# CC2640.net
KiCad netlist of a schematic drawn in Altium Designer
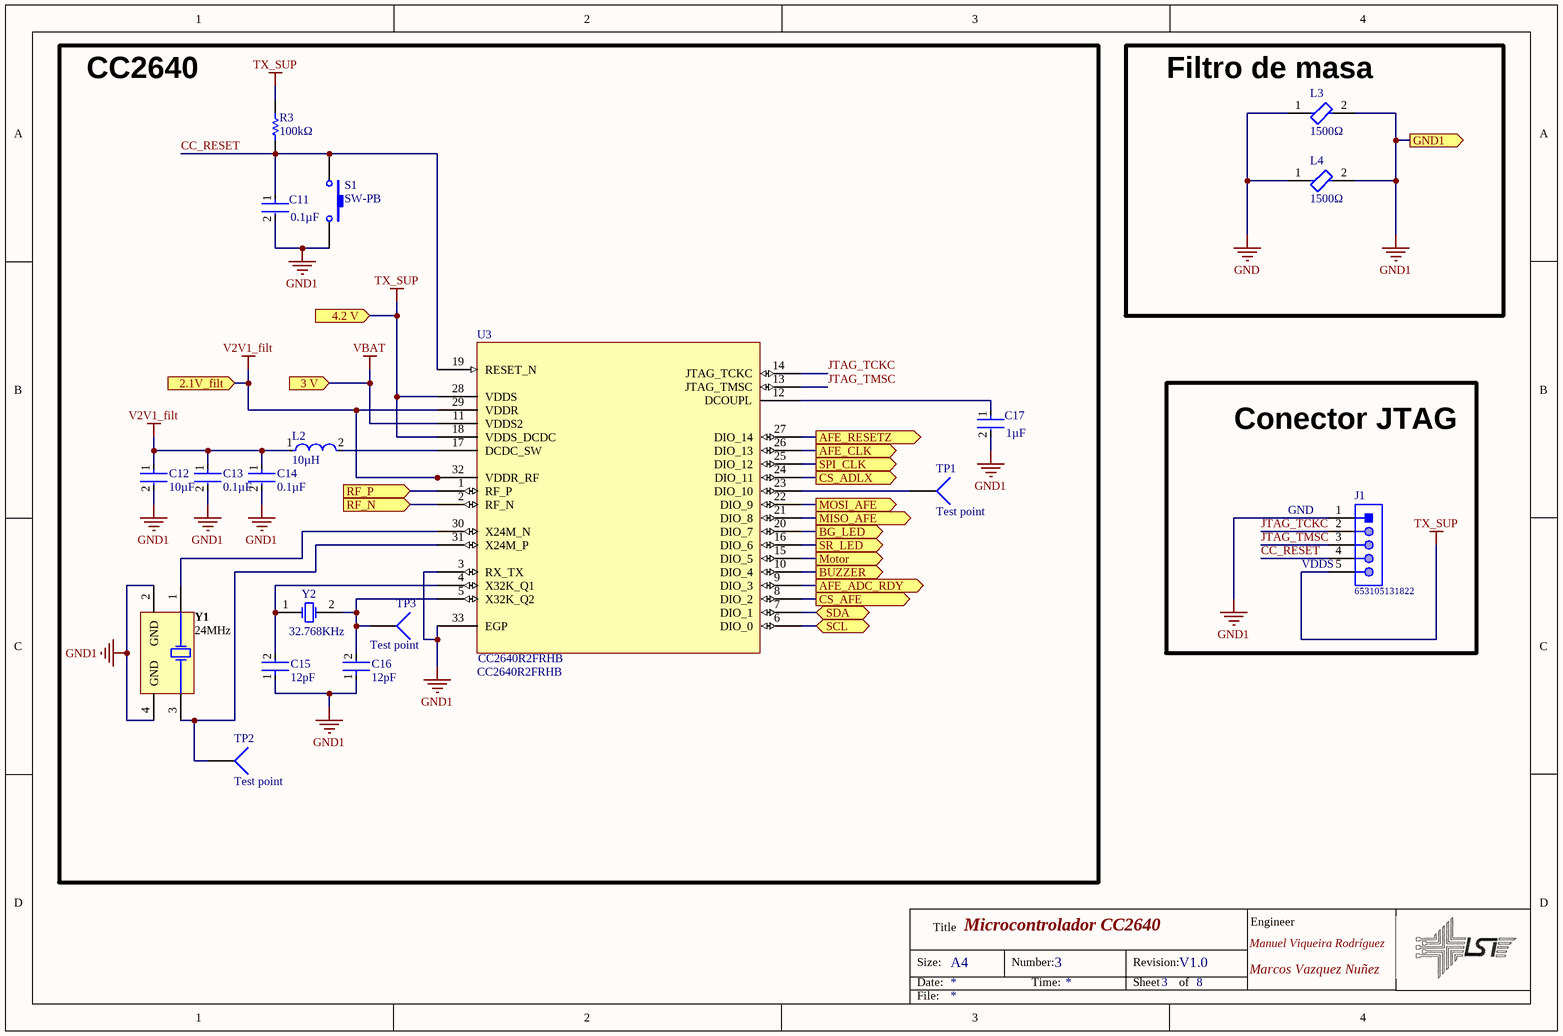
[diagram p0: CC2640.SchDoc]

(export (version "E")
  (design (tool "Eeschema 10.0.6"))
  (components
    (comp (ref "C11")
      (value "0.1µF")
      (footprint "FP-CL10-IPC_B")
      (description "Cap Ceramic 10uF 10V X5R ±10% Pad SMD 0603 +85°C T/R")
      (fields (field (name "TOLERANCE") "10%"))
      (libsource (lib "Altium Content Vault") (part "b4654b650e69147ec39a6b967a45e02"))
    )
    (comp (ref "C12")
      (value "10µF")
      (footprint "FP-CL10-IPC_B")
      (description "Cap Ceramic 10uF 10V X5R ±10% Pad SMD 0603 +85°C T/R")
      (fields (field (name "TOLERANCE") "10%"))
      (libsource (lib "Altium Content Vault") (part "b4654b650e69147ec39a6b967a45e02"))
    )
    (comp (ref "C13")
      (value "0.1µF")
      (footprint "FP-CL10-IPC_B")
      (description "Cap Ceramic 10uF 10V X5R ±10% Pad SMD 0603 +85°C T/R")
      (fields (field (name "TOLERANCE") "10%"))
      (libsource (lib "Altium Content Vault") (part "b4654b650e69147ec39a6b967a45e02"))
    )
    (comp (ref "C14")
      (value "0.1µF")
      (footprint "FP-CL10-IPC_B")
      (description "Cap Ceramic 10uF 10V X5R ±10% Pad SMD 0603 +85°C T/R")
      (fields (field (name "TOLERANCE") "10%"))
      (libsource (lib "Altium Content Vault") (part "b4654b650e69147ec39a6b967a45e02"))
    )
    (comp (ref "C15")
      (value "12pF")
      (footprint "FP-CL10-IPC_B")
      (description "Cap Ceramic 10uF 10V X5R ±10% Pad SMD 0603 +85°C T/R")
      (fields (field (name "TOLERANCE") "10%"))
      (libsource (lib "Altium Content Vault") (part "b4654b650e69147ec39a6b967a45e02"))
    )
    (comp (ref "C16")
      (value "12pF")
      (footprint "FP-CL10-IPC_B")
      (description "Cap Ceramic 10uF 10V X5R ±10% Pad SMD 0603 +85°C T/R")
      (fields (field (name "TOLERANCE") "10%"))
      (libsource (lib "Altium Content Vault") (part "b4654b650e69147ec39a6b967a45e02"))
    )
    (comp (ref "C17")
      (value "1µF")
      (footprint "FP-CL10-IPC_B")
      (description "Cap Ceramic 10uF 10V X5R ±10% Pad SMD 0603 +85°C T/R")
      (fields (field (name "TOLERANCE") "10%"))
      (libsource (lib "Altium Content Vault") (part "b4654b650e69147ec39a6b967a45e02"))
    )
    (comp (ref "J1")
      (value "653105131822")
      (footprint "653105131822")
      (description "Male Shrouded Header WR-WTB, SMT, Right Angled, pitch 1.25 mm, 1 x 5 position")
      (fields (field (name "MANUFACTURER") "Wurth Elektronik") (field (name "PUBLISHER") "WurthElektronik"))
      (libsource (lib "Altium Content Vault") (part "WE-CN-1P-M-R5"))
    )
    (comp (ref "L2")
      (value "10µH")
      (footprint "FP-LQW15AN_00-W0_6-0_1-MFG")
      (description "Wire Wound RF Inductor 15nH ±5% 460mA 0.16Ω 0402 (1005)")
      (fields (field (name "TOLERANCE") "5%"))
      (libsource (lib "Altium Content Vault") (part "725321dda6339637d4d059423bc1c3c"))
    )
    (comp (ref "L3")
      (value "1500Ω")
      (footprint "FP-BLM18-0_15-t0_8-IPC_C")
      (description "Chip Ferrite Bead, 0603, 1500Ω @ 100MHz, 0.5Ω, 25%, 500mA")
      (fields (field (name "TOLERANCE") "25%"))
      (libsource (lib "Altium Content Vault") (part "5f30dd21d616792df468990f7003faa"))
    )
    (comp (ref "L4")
      (value "1500Ω")
      (footprint "FP-BLM18-0_15-t0_8-IPC_C")
      (description "Chip Ferrite Bead, 0603, 1500Ω @ 100MHz, 0.5Ω, 25%, 500mA")
      (fields (field (name "TOLERANCE") "25%"))
      (libsource (lib "Altium Content Vault") (part "5f30dd21d616792df468990f7003faa"))
    )
    (comp (ref "R3")
      (value "100kΩ")
      (footprint "RESC0603X28X15ML05T05")
      (fields (field (name "MANUFACTURER") "Vishay Dale") (field (name "PART NUMBER") "CRCW020120K0JNED"))
      (libsource (lib "Altium Content Vault") (part "RES"))
    )
    (comp (ref "S1")
      (value "SW-PB")
      (footprint "SPST-2")
      (description "Switch")
      (fields (field (name "PUBLISHER") "Altium Limited"))
      (libsource (lib "Miscellaneous Devices") (part "SW-PB"))
    )
    (comp (ref "TP1")
      (value "Test point")
      (footprint "PIN1")
      (description "Socket")
      (fields (field (name "PUBLISHER") "Altium Limited"))
      (libsource (lib "Miscellaneous Connectors") (part "Socket"))
    )
    (comp (ref "TP2")
      (value "Test point")
      (footprint "PIN1")
      (description "Socket")
      (fields (field (name "PUBLISHER") "Altium Limited"))
      (libsource (lib "Miscellaneous Connectors") (part "Socket"))
    )
    (comp (ref "TP3")
      (value "Test point")
      (footprint "PIN1")
      (description "Socket")
      (fields (field (name "PUBLISHER") "Altium Limited"))
      (libsource (lib "Miscellaneous Connectors") (part "Socket"))
    )
    (comp (ref "U3")
      (value "CC2640R2FRHB")
      (footprint "DEOP2021-Calle-Payno")
      (libsource (lib "DEOP2021") (part "CC2640R2FRHB"))
    )
    (comp (ref "Y1")
      (value "24MHz")
      (footprint "ABRA-ABM3B-4_V")
      (description "Ceramic SMD Crystal, 24 MHz, +/- 20 ppm, 50 Ohm, -20 to 70 degC, 4-Pin SMD, RoHS, Tape and Reel")
      (libsource (lib "Altium Content Vault") (part "XTAL-1-3-4"))
    )
    (comp (ref "Y2")
      (value "32.768KHz")
      (footprint "R38")
      (description "Crystal Oscillator")
      (fields (field (name "PUBLISHER") "Altium Limited"))
      (libsource (lib "Miscellaneous Devices") (part "XTAL"))
    )
  )
  (nets
    (net (code "1") (name "/AFE_ADC_RDY") (class "Default")
      (node (ref "U3") (pin "9") (pinfunction "DIO_3_9") (pintype "bidirectional"))
    )
    (net (code "2") (name "/AFE_CLK") (class "Default")
      (node (ref "U3") (pin "26") (pinfunction "DIO_13_26") (pintype "bidirectional"))
    )
    (net (code "3") (name "/AFE_RESETZ") (class "Default")
      (node (ref "U3") (pin "27") (pinfunction "DIO_14_27") (pintype "bidirectional"))
    )
    (net (code "4") (name "/BG_LED") (class "Default")
      (node (ref "U3") (pin "20") (pinfunction "DIO_7_20") (pintype "bidirectional"))
    )
    (net (code "5") (name "/BUZZER") (class "Default")
      (node (ref "U3") (pin "10") (pinfunction "DIO_4_10") (pintype "bidirectional"))
    )
    (net (code "6") (name "/CC_RESET") (class "Default")
      (node (ref "C11") (pin "1") (pinfunction "1_1") (pintype "passive"))
      (node (ref "J1") (pin "4") (pinfunction "4_4") (pintype "passive"))
      (node (ref "R3") (pin "1") (pinfunction "1_1") (pintype "passive"))
      (node (ref "S1") (pin "1") (pinfunction "1_1") (pintype "passive"))
      (node (ref "U3") (pin "19") (pinfunction "RESET_N_19") (pintype "input"))
    )
    (net (code "7") (name "/CS_ADLX") (class "Default")
      (node (ref "U3") (pin "24") (pinfunction "DIO_11_24") (pintype "bidirectional"))
    )
    (net (code "8") (name "/CS_AFE") (class "Default")
      (node (ref "U3") (pin "8") (pinfunction "DIO_2_8") (pintype "bidirectional"))
    )
    (net (code "9") (name "/JTAG_TCKC") (class "Default")
      (node (ref "J1") (pin "2") (pinfunction "2_2") (pintype "passive"))
      (node (ref "U3") (pin "14") (pinfunction "JTAG_TCKC_14") (pintype "bidirectional"))
    )
    (net (code "10") (name "/JTAG_TMSC") (class "Default")
      (node (ref "J1") (pin "3") (pinfunction "3_3") (pintype "passive"))
      (node (ref "U3") (pin "13") (pinfunction "JTAG_TMSC_13") (pintype "bidirectional"))
    )
    (net (code "11") (name "/MISO_AFE") (class "Default")
      (node (ref "U3") (pin "21") (pinfunction "DIO_8_21") (pintype "bidirectional"))
    )
    (net (code "12") (name "/MOSI_AFE") (class "Default")
      (node (ref "U3") (pin "22") (pinfunction "DIO_9_22") (pintype "bidirectional"))
    )
    (net (code "13") (name "/Motor") (class "Default")
      (node (ref "U3") (pin "15") (pinfunction "DIO_5_15") (pintype "bidirectional"))
    )
    (net (code "14") (name "/RF_N") (class "Default")
      (node (ref "U3") (pin "2") (pinfunction "RF_N_2") (pintype "bidirectional"))
    )
    (net (code "15") (name "/RF_P") (class "Default")
      (node (ref "U3") (pin "1") (pinfunction "RF_P_1") (pintype "bidirectional"))
    )
    (net (code "16") (name "/SCL") (class "Default")
      (node (ref "U3") (pin "6") (pinfunction "DIO_0_6") (pintype "bidirectional"))
    )
    (net (code "17") (name "/SDA") (class "Default")
      (node (ref "U3") (pin "7") (pinfunction "DIO_1_7") (pintype "bidirectional"))
    )
    (net (code "18") (name "/SPI_CLK") (class "Default")
      (node (ref "U3") (pin "25") (pinfunction "DIO_12_25") (pintype "bidirectional"))
    )
    (net (code "19") (name "/SR_LED") (class "Default")
      (node (ref "U3") (pin "16") (pinfunction "DIO_6_16") (pintype "bidirectional"))
    )
    (net (code "20") (name "GND") (class "Default")
      (node (ref "L3") (pin "1") (pinfunction "1_1") (pintype "passive"))
      (node (ref "L4") (pin "1") (pinfunction "1_1") (pintype "passive"))
    )
    (net (code "21") (name "GND1") (class "Default")
      (node (ref "C11") (pin "2") (pinfunction "2_2") (pintype "passive"))
      (node (ref "C12") (pin "2") (pinfunction "2_2") (pintype "passive"))
      (node (ref "C13") (pin "2") (pinfunction "2_2") (pintype "passive"))
      (node (ref "C14") (pin "2") (pinfunction "2_2") (pintype "passive"))
      (node (ref "C15") (pin "1") (pinfunction "1_1") (pintype "passive"))
      (node (ref "C16") (pin "1") (pinfunction "1_1") (pintype "passive"))
      (node (ref "C17") (pin "2") (pinfunction "2_2") (pintype "passive"))
      (node (ref "J1") (pin "1") (pinfunction "1_1") (pintype "passive"))
      (node (ref "L3") (pin "2") (pinfunction "2_2") (pintype "passive"))
      (node (ref "L4") (pin "2") (pinfunction "2_2") (pintype "passive"))
      (node (ref "S1") (pin "2") (pinfunction "2_2") (pintype "passive"))
      (node (ref "U3") (pin "3") (pinfunction "RX_TX_3") (pintype "bidirectional"))
      (node (ref "U3") (pin "33") (pinfunction "EGP_33") (pintype "power_in"))
      (node (ref "Y1") (pin "2") (pinfunction "GND_2") (pintype "power_in"))
      (node (ref "Y1") (pin "4") (pinfunction "GND_4") (pintype "power_in"))
    )
    (net (code "22") (name "Net-(U3-DCDC_SW)") (class "Default")
      (node (ref "L2") (pin "2") (pinfunction "2_2") (pintype "passive"))
      (node (ref "U3") (pin "17") (pinfunction "DCDC_SW_17") (pintype "power_in"))
    )
    (net (code "23") (name "Net-(U3-DCOUPL)") (class "Default")
      (node (ref "C17") (pin "1") (pinfunction "1_1") (pintype "passive"))
      (node (ref "U3") (pin "12") (pinfunction "DCOUPL_12") (pintype "power_in"))
    )
    (net (code "24") (name "Net-(U3-DIO_10)") (class "Default")
      (node (ref "TP1") (pin "1") (pinfunction "1_1") (pintype "passive"))
      (node (ref "U3") (pin "23") (pinfunction "DIO_10_23") (pintype "bidirectional"))
    )
    (net (code "25") (name "Net-(U3-X24M_N)") (class "Default")
      (node (ref "U3") (pin "30") (pinfunction "X24M_N_30") (pintype "bidirectional"))
      (node (ref "Y1") (pin "1") (pinfunction "X1_1") (pintype "passive"))
    )
    (net (code "26") (name "Net-(U3-X24M_P)") (class "Default")
      (node (ref "TP2") (pin "1") (pinfunction "1_1") (pintype "passive"))
      (node (ref "U3") (pin "31") (pinfunction "X24M_P_31") (pintype "bidirectional"))
      (node (ref "Y1") (pin "3") (pinfunction "X2_3") (pintype "passive"))
    )
    (net (code "27") (name "Net-(U3-X32K_Q1)") (class "Default")
      (node (ref "C15") (pin "2") (pinfunction "2_2") (pintype "passive"))
      (node (ref "U3") (pin "4") (pinfunction "X32K_Q1_4") (pintype "bidirectional"))
      (node (ref "Y2") (pin "1") (pinfunction "OSC1_1") (pintype "passive"))
    )
    (net (code "28") (name "Net-(U3-X32K_Q2)") (class "Default")
      (node (ref "C16") (pin "2") (pinfunction "2_2") (pintype "passive"))
      (node (ref "TP3") (pin "1") (pinfunction "1_1") (pintype "passive"))
      (node (ref "U3") (pin "5") (pinfunction "X32K_Q2_5") (pintype "bidirectional"))
      (node (ref "Y2") (pin "2") (pinfunction "OSC2_2") (pintype "passive"))
    )
    (net (code "29") (name "TX_SUP") (class "Default")
      (node (ref "J1") (pin "5") (pinfunction "5_5") (pintype "passive"))
      (node (ref "R3") (pin "2") (pinfunction "2_2") (pintype "passive"))
      (node (ref "U3") (pin "18") (pinfunction "VDDS_DCDC_18") (pintype "power_in"))
      (node (ref "U3") (pin "28") (pinfunction "VDDS_28") (pintype "power_in"))
    )
    (net (code "30") (name "V2V1_filt") (class "Default")
      (node (ref "C12") (pin "1") (pinfunction "1_1") (pintype "passive"))
      (node (ref "C13") (pin "1") (pinfunction "1_1") (pintype "passive"))
      (node (ref "C14") (pin "1") (pinfunction "1_1") (pintype "passive"))
      (node (ref "L2") (pin "1") (pinfunction "1_1") (pintype "passive"))
      (node (ref "U3") (pin "29") (pinfunction "VDDR_29") (pintype "power_in"))
      (node (ref "U3") (pin "32") (pinfunction "VDDR_RF_32") (pintype "power_in"))
    )
    (net (code "31") (name "VBAT") (class "Default")
      (node (ref "U3") (pin "11") (pinfunction "VDDS2_11") (pintype "power_in"))
    )
  )
)
